# nrf51822-button.net
KiCad netlist of a schematic drawn in EAGLE
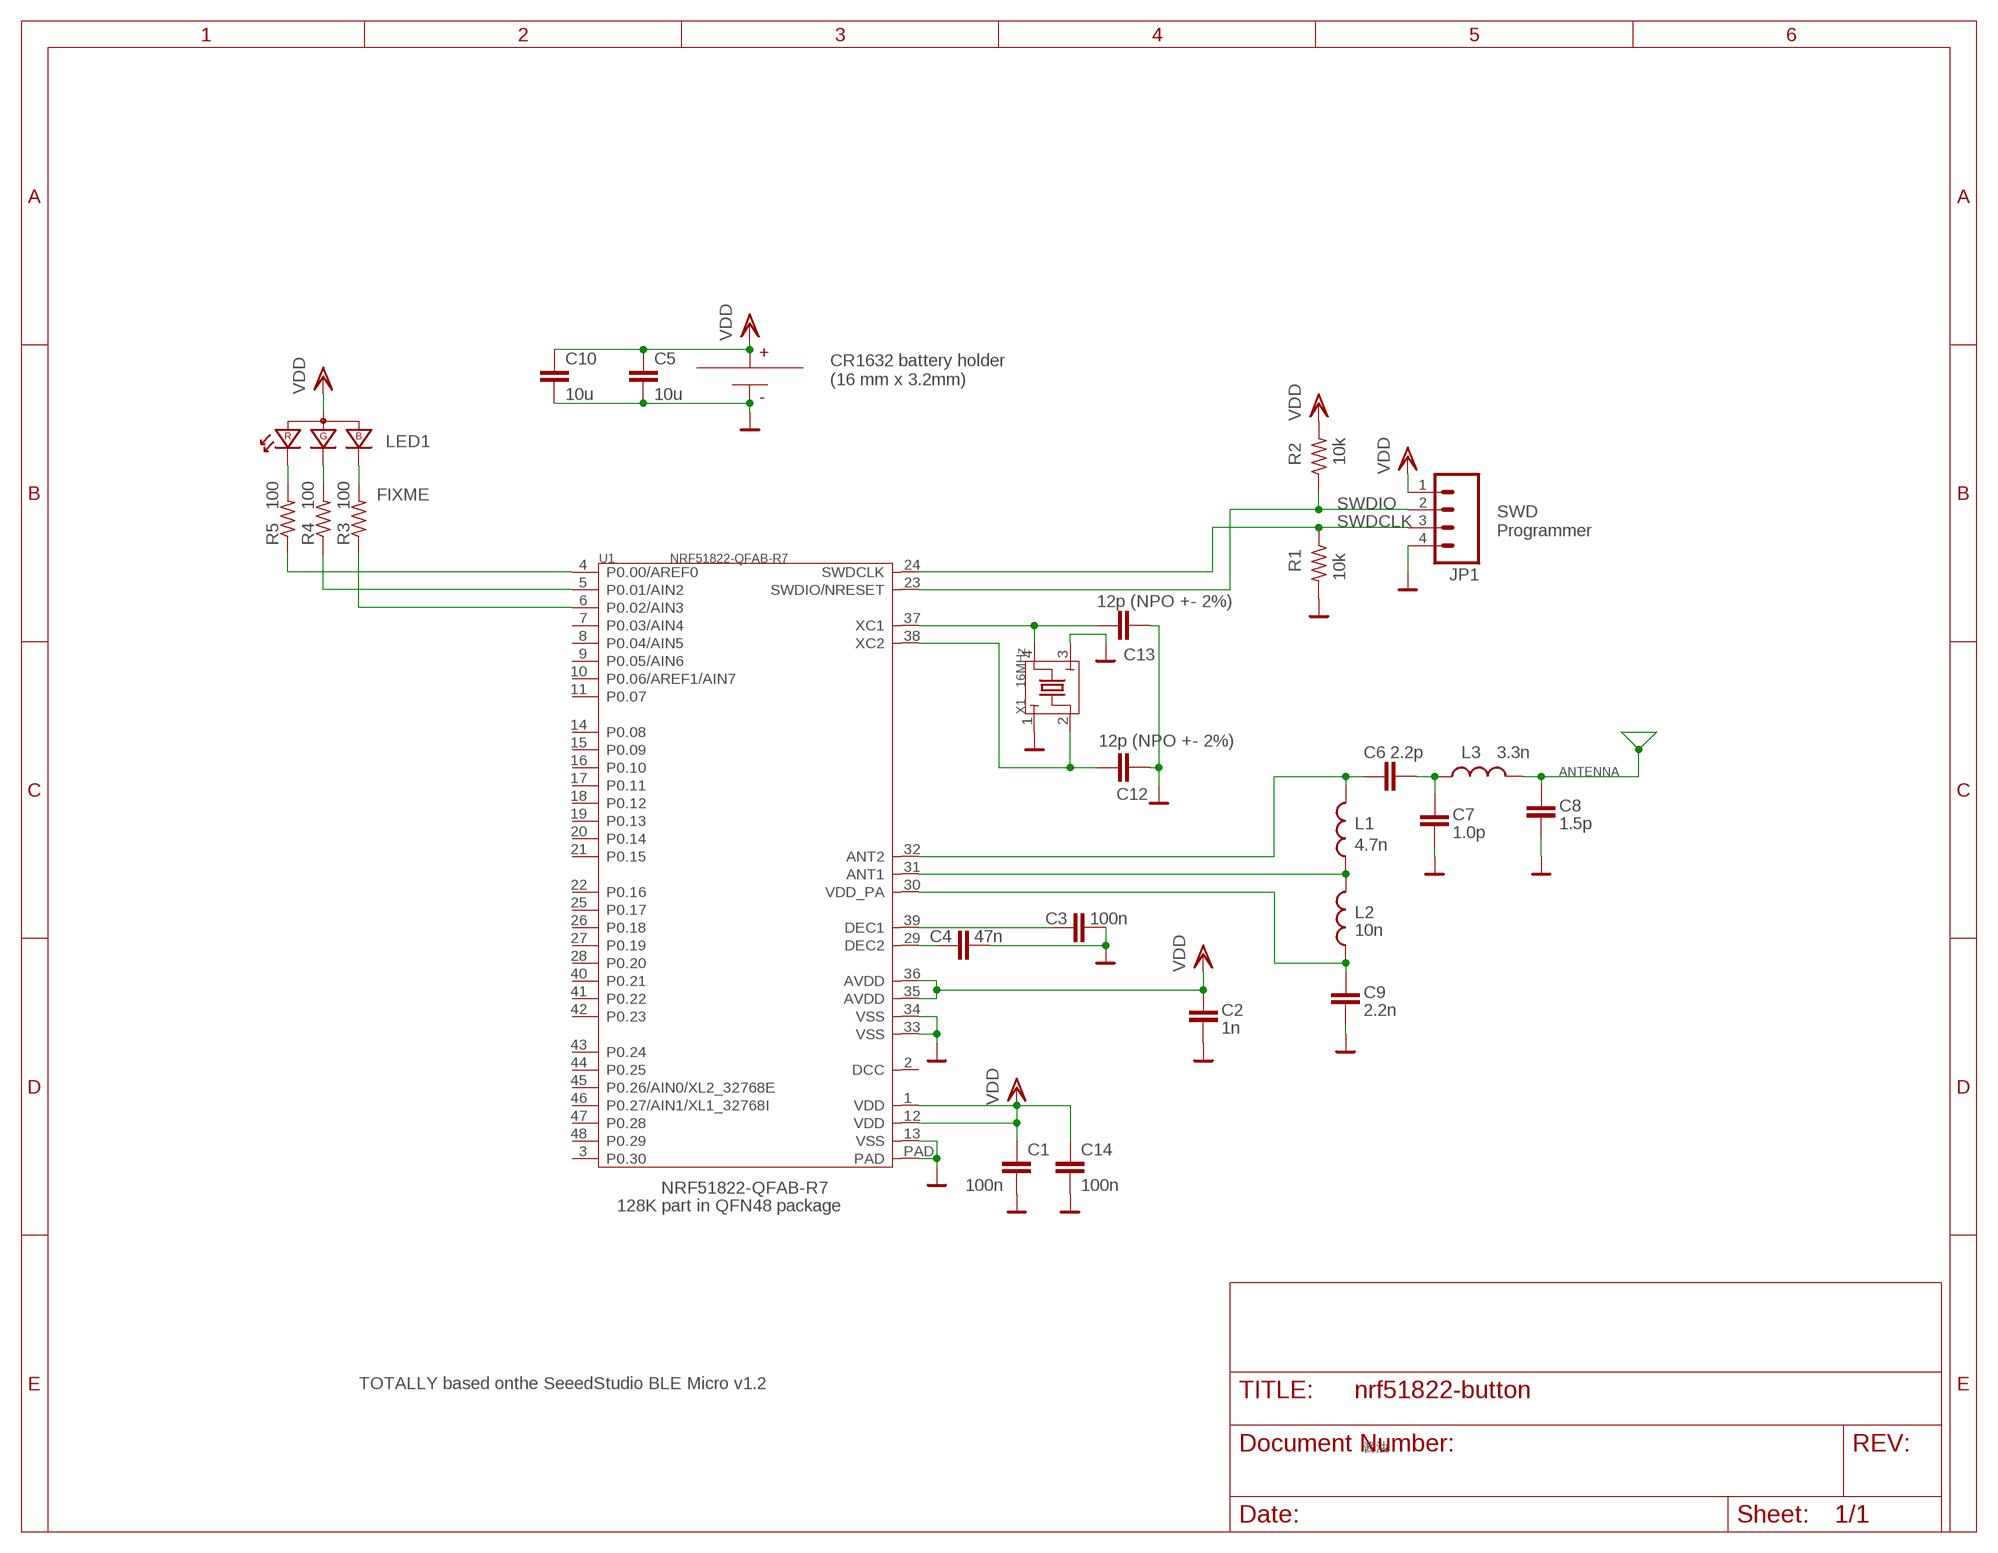
[diagram p0: schematic, sheet 1]

(export (version "E")
  (design (tool "Eeschema 10.0.6"))
  (components
    (comp (ref "B1")
      (value "CON-COINCEL-HOLDER-KEYSTONE-3012TR")
      (footprint "eagle-import:16MM-COINCELL-KEYSTONE")
      (libsource (lib "eagle-import") (part "CON-COINCEL-HOLDER-KEYSTONE-3012TR"))
    )
    (comp (ref "C1")
      (value "100n")
      (footprint "eagle-import:.0402-C-NOSILK")
      (libsource (lib "eagle-import") (part "C-EU0402-C-NOSILK"))
    )
    (comp (ref "C2")
      (value "1n")
      (footprint "eagle-import:.0402-C-NOSILK")
      (libsource (lib "eagle-import") (part "C-EU0402-C-NOSILK"))
    )
    (comp (ref "C3")
      (value "100n")
      (footprint "eagle-import:.0402-C-NOSILK")
      (libsource (lib "eagle-import") (part "C-EU0402-C-NOSILK"))
    )
    (comp (ref "C4")
      (value "47n")
      (footprint "eagle-import:.0402-C-NOSILK")
      (libsource (lib "eagle-import") (part "C-EU0402-C-NOSILK"))
    )
    (comp (ref "C5")
      (value "10u")
      (footprint "eagle-import:.0805-B-NOSILK")
      (libsource (lib "eagle-import") (part "C-EU0805-B-NOSILK"))
    )
    (comp (ref "C6")
      (value "2.2p")
      (footprint "eagle-import:.0402-C-NOSILK")
      (libsource (lib "eagle-import") (part "C-EU0402-C-NOSILK"))
    )
    (comp (ref "C7")
      (value "1.0p")
      (footprint "eagle-import:.0402-C-NOSILK")
      (libsource (lib "eagle-import") (part "C-EU0402-C-NOSILK"))
    )
    (comp (ref "C8")
      (value "1.5p")
      (footprint "eagle-import:.0402-C-NOSILK")
      (libsource (lib "eagle-import") (part "C-EU0402-C-NOSILK"))
    )
    (comp (ref "C9")
      (value "2.2n")
      (footprint "eagle-import:.0402-C-NOSILK")
      (libsource (lib "eagle-import") (part "C-EU0402-C-NOSILK"))
    )
    (comp (ref "C10")
      (value "10u")
      (footprint "eagle-import:.0805-B-NOSILK")
      (libsource (lib "eagle-import") (part "C-EU0805-B-NOSILK"))
    )
    (comp (ref "C12")
      (value "12p (NPO +- 2%)")
      (footprint "eagle-import:.0402-C-NOSILK")
      (libsource (lib "eagle-import") (part "C-EU0402-C-NOSILK"))
    )
    (comp (ref "C13")
      (value "12p (NPO +- 2%)")
      (footprint "eagle-import:.0402-C-NOSILK")
      (libsource (lib "eagle-import") (part "C-EU0402-C-NOSILK"))
    )
    (comp (ref "C14")
      (value "100n")
      (footprint "eagle-import:.0402-C-NOSILK")
      (libsource (lib "eagle-import") (part "C-EU0402-C-NOSILK"))
    )
    (comp (ref "JP1")
      (value "M041.27MM")
      (footprint "eagle-import:1X04-1.27MM")
      (libsource (lib "eagle-import") (part "M041.27MM"))
    )
    (comp (ref "L1")
      (value "4.7n")
      (footprint "eagle-import:.0402-C-NOSILK")
      (libsource (lib "eagle-import") (part "L-US0402-C-NOSILK"))
    )
    (comp (ref "L2")
      (value "10n")
      (footprint "eagle-import:.0402-C-NOSILK")
      (libsource (lib "eagle-import") (part "L-US0402-C-NOSILK"))
    )
    (comp (ref "L3")
      (value "3.3n")
      (footprint "eagle-import:.0402-C-NOSILK")
      (libsource (lib "eagle-import") (part "L-US0402-C-NOSILK"))
    )
    (comp (ref "LED1")
      (value "LED_RGB_COMMON_ANODE-1.6X1.26")
      (footprint "eagle-import:KINGBRITE_RGBLED_1.6X1.26")
      (libsource (lib "eagle-import") (part "LED_RGB_COMMON_ANODE-1.6X1.26"))
    )
    (comp (ref "R1")
      (value "10k")
      (footprint "eagle-import:.0402-C-NOSILK")
      (libsource (lib "eagle-import") (part "R-US_0402-C-NOSILK"))
    )
    (comp (ref "R2")
      (value "10k")
      (footprint "eagle-import:.0402-C-NOSILK")
      (libsource (lib "eagle-import") (part "R-US_0402-C-NOSILK"))
    )
    (comp (ref "R3")
      (value "100")
      (footprint "eagle-import:.0402-C-NOSILK")
      (libsource (lib "eagle-import") (part "R-US_0402-C-NOSILK"))
    )
    (comp (ref "R4")
      (value "100")
      (footprint "eagle-import:.0402-C-NOSILK")
      (libsource (lib "eagle-import") (part "R-US_0402-C-NOSILK"))
    )
    (comp (ref "R5")
      (value "100")
      (footprint "eagle-import:.0402-C-NOSILK")
      (libsource (lib "eagle-import") (part "R-US_0402-C-NOSILK"))
    )
    (comp (ref "U1")
      (value "NRF51822-QFAB-R7")
      (footprint "eagle-import:QFN48-6X6MM")
      (libsource (lib "eagle-import") (part "NRF51822"))
    )
    (comp (ref "X1")
      (value "16MHz")
      (footprint "eagle-import:2520")
      (libsource (lib "eagle-import") (part "CRYSTAL'-2520'"))
    )
  )
  (nets
    (net (code "1") (name "/ANTENNA") (class "Default")
      (node (ref "C8") (pin "2") (pinfunction "2_2") (pintype "passive"))
      (node (ref "L3") (pin "2") (pinfunction "2_2") (pintype "passive"))
    )
    (net (code "2") (name "/SWDCLK") (class "Default")
      (node (ref "JP1") (pin "3") (pinfunction "3_3") (pintype "passive"))
      (node (ref "R1") (pin "1") (pinfunction "1_1") (pintype "passive"))
      (node (ref "U1") (pin "24") (pinfunction "SWDCLK_24") (pintype "bidirectional"))
    )
    (net (code "3") (name "/SWDIO") (class "Default")
      (node (ref "JP1") (pin "2") (pinfunction "2_2") (pintype "passive"))
      (node (ref "R2") (pin "1") (pinfunction "1_1") (pintype "passive"))
      (node (ref "U1") (pin "23") (pinfunction "SWDIO/NRESET_23") (pintype "bidirectional"))
    )
    (net (code "4") (name "GND") (class "Default")
      (node (ref "B1") (pin "NEG") (pinfunction "NEG_NEG") (pintype "power_in"))
      (node (ref "C1") (pin "2") (pinfunction "2_2") (pintype "passive"))
      (node (ref "C10") (pin "2") (pinfunction "2_2") (pintype "passive"))
      (node (ref "C12") (pin "2") (pinfunction "2_2") (pintype "passive"))
      (node (ref "C13") (pin "2") (pinfunction "2_2") (pintype "passive"))
      (node (ref "C14") (pin "2") (pinfunction "2_2") (pintype "passive"))
      (node (ref "C2") (pin "2") (pinfunction "2_2") (pintype "passive"))
      (node (ref "C3") (pin "2") (pinfunction "2_2") (pintype "passive"))
      (node (ref "C4") (pin "2") (pinfunction "2_2") (pintype "passive"))
      (node (ref "C5") (pin "2") (pinfunction "2_2") (pintype "passive"))
      (node (ref "C7") (pin "1") (pinfunction "1_1") (pintype "passive"))
      (node (ref "C8") (pin "1") (pinfunction "1_1") (pintype "passive"))
      (node (ref "C9") (pin "2") (pinfunction "2_2") (pintype "passive"))
      (node (ref "JP1") (pin "4") (pinfunction "4_4") (pintype "passive"))
      (node (ref "R1") (pin "2") (pinfunction "2_2") (pintype "passive"))
      (node (ref "U1") (pin "13") (pinfunction "VSS_13") (pintype "bidirectional"))
      (node (ref "U1") (pin "33") (pinfunction "VSS_33") (pintype "bidirectional"))
      (node (ref "U1") (pin "34") (pinfunction "VSS_34") (pintype "bidirectional"))
      (node (ref "U1") (pin "PAD") (pinfunction "PAD_PAD") (pintype "bidirectional"))
      (node (ref "X1") (pin "1") (pinfunction "1_1") (pintype "bidirectional"))
      (node (ref "X1") (pin "3") (pinfunction "3_3") (pintype "bidirectional"))
    )
    (net (code "5") (name "Net-(C6-Pad2)") (class "Default")
      (node (ref "C6") (pin "2") (pinfunction "2_2") (pintype "passive"))
      (node (ref "C7") (pin "2") (pinfunction "2_2") (pintype "passive"))
      (node (ref "L3") (pin "1") (pinfunction "1_1") (pintype "passive"))
    )
    (net (code "6") (name "Net-(LED1-BK)") (class "Default")
      (node (ref "LED1") (pin "1") (pinfunction "BK_1") (pintype "passive"))
      (node (ref "R3") (pin "2") (pinfunction "2_2") (pintype "passive"))
    )
    (net (code "7") (name "Net-(LED1-GK)") (class "Default")
      (node (ref "LED1") (pin "4") (pinfunction "GK_4") (pintype "passive"))
      (node (ref "R4") (pin "2") (pinfunction "2_2") (pintype "passive"))
    )
    (net (code "8") (name "Net-(LED1-RK)") (class "Default")
      (node (ref "LED1") (pin "3") (pinfunction "RK_3") (pintype "passive"))
      (node (ref "R5") (pin "2") (pinfunction "2_2") (pintype "passive"))
    )
    (net (code "9") (name "Net-(U1-ANT1)") (class "Default")
      (node (ref "L1") (pin "1") (pinfunction "1_1") (pintype "passive"))
      (node (ref "L2") (pin "2") (pinfunction "2_2") (pintype "passive"))
      (node (ref "U1") (pin "31") (pinfunction "ANT1_31") (pintype "bidirectional"))
    )
    (net (code "10") (name "Net-(U1-ANT2)") (class "Default")
      (node (ref "C6") (pin "1") (pinfunction "1_1") (pintype "passive"))
      (node (ref "L1") (pin "2") (pinfunction "2_2") (pintype "passive"))
      (node (ref "U1") (pin "32") (pinfunction "ANT2_32") (pintype "bidirectional"))
    )
    (net (code "11") (name "Net-(U1-DEC1)") (class "Default")
      (node (ref "C3") (pin "1") (pinfunction "1_1") (pintype "passive"))
      (node (ref "U1") (pin "39") (pinfunction "DEC1_39") (pintype "bidirectional"))
    )
    (net (code "12") (name "Net-(U1-DEC2)") (class "Default")
      (node (ref "C4") (pin "1") (pinfunction "1_1") (pintype "passive"))
      (node (ref "U1") (pin "29") (pinfunction "DEC2_29") (pintype "bidirectional"))
    )
    (net (code "13") (name "Net-(U1-P0.00{slash}AREF0)") (class "Default")
      (node (ref "R5") (pin "1") (pinfunction "1_1") (pintype "passive"))
      (node (ref "U1") (pin "4") (pinfunction "P0.00/AREF0_4") (pintype "bidirectional"))
    )
    (net (code "14") (name "Net-(U1-P0.01{slash}AIN2)") (class "Default")
      (node (ref "R4") (pin "1") (pinfunction "1_1") (pintype "passive"))
      (node (ref "U1") (pin "5") (pinfunction "P0.01/AIN2_5") (pintype "bidirectional"))
    )
    (net (code "15") (name "Net-(U1-P0.02{slash}AIN3)") (class "Default")
      (node (ref "R3") (pin "1") (pinfunction "1_1") (pintype "passive"))
      (node (ref "U1") (pin "6") (pinfunction "P0.02/AIN3_6") (pintype "bidirectional"))
    )
    (net (code "16") (name "Net-(U1-VDD_PA)") (class "Default")
      (node (ref "C9") (pin "1") (pinfunction "1_1") (pintype "passive"))
      (node (ref "L2") (pin "1") (pinfunction "1_1") (pintype "passive"))
      (node (ref "U1") (pin "30") (pinfunction "VDD_PA_30") (pintype "bidirectional"))
    )
    (net (code "17") (name "Net-(U1-XC1)") (class "Default")
      (node (ref "C13") (pin "1") (pinfunction "1_1") (pintype "passive"))
      (node (ref "U1") (pin "37") (pinfunction "XC1_37") (pintype "bidirectional"))
      (node (ref "X1") (pin "4") (pinfunction "4_4") (pintype "passive"))
    )
    (net (code "18") (name "Net-(U1-XC2)") (class "Default")
      (node (ref "C12") (pin "1") (pinfunction "1_1") (pintype "passive"))
      (node (ref "U1") (pin "38") (pinfunction "XC2_38") (pintype "bidirectional"))
      (node (ref "X1") (pin "2") (pinfunction "2_2") (pintype "passive"))
    )
    (net (code "19") (name "VDD") (class "Default")
      (node (ref "B1") (pin "POS@1") (pinfunction "POS_POS@1") (pintype "power_in"))
      (node (ref "B1") (pin "POS@2") (pinfunction "POS_POS@2") (pintype "power_in"))
      (node (ref "C1") (pin "1") (pinfunction "1_1") (pintype "passive"))
      (node (ref "C10") (pin "1") (pinfunction "1_1") (pintype "passive"))
      (node (ref "C14") (pin "1") (pinfunction "1_1") (pintype "passive"))
      (node (ref "C2") (pin "1") (pinfunction "1_1") (pintype "passive"))
      (node (ref "C5") (pin "1") (pinfunction "1_1") (pintype "passive"))
      (node (ref "JP1") (pin "1") (pinfunction "1_1") (pintype "passive"))
      (node (ref "LED1") (pin "2") (pinfunction "COMMON_ANODE_2") (pintype "passive"))
      (node (ref "R2") (pin "2") (pinfunction "2_2") (pintype "passive"))
      (node (ref "U1") (pin "1") (pinfunction "VDD_1") (pintype "bidirectional"))
      (node (ref "U1") (pin "12") (pinfunction "VDD_12") (pintype "bidirectional"))
      (node (ref "U1") (pin "35") (pinfunction "AVDD_35") (pintype "bidirectional"))
      (node (ref "U1") (pin "36") (pinfunction "AVDD_36") (pintype "bidirectional"))
    )
    (net (code "20") (name "unconnected-(U1-DCC-Pad2)") (class "Default")
      (node (ref "U1") (pin "2") (pinfunction "DCC_2") (pintype "bidirectional"))
    )
    (net (code "21") (name "unconnected-(U1-P0.03{slash}AIN4-Pad7)") (class "Default")
      (node (ref "U1") (pin "7") (pinfunction "P0.03/AIN4_7") (pintype "bidirectional"))
    )
    (net (code "22") (name "unconnected-(U1-P0.04{slash}AIN5-Pad8)") (class "Default")
      (node (ref "U1") (pin "8") (pinfunction "P0.04/AIN5_8") (pintype "bidirectional"))
    )
    (net (code "23") (name "unconnected-(U1-P0.05{slash}AIN6-Pad9)") (class "Default")
      (node (ref "U1") (pin "9") (pinfunction "P0.05/AIN6_9") (pintype "bidirectional"))
    )
    (net (code "24") (name "unconnected-(U1-P0.06{slash}AREF1{slash}AIN7-Pad10)") (class "Default")
      (node (ref "U1") (pin "10") (pinfunction "P0.06/AREF1/AIN7_10") (pintype "bidirectional"))
    )
    (net (code "25") (name "unconnected-(U1-P0.07-Pad11)") (class "Default")
      (node (ref "U1") (pin "11") (pinfunction "P0.07_11") (pintype "bidirectional"))
    )
    (net (code "26") (name "unconnected-(U1-P0.08-Pad14)") (class "Default")
      (node (ref "U1") (pin "14") (pinfunction "P0.08_14") (pintype "bidirectional"))
    )
    (net (code "27") (name "unconnected-(U1-P0.09-Pad15)") (class "Default")
      (node (ref "U1") (pin "15") (pinfunction "P0.09_15") (pintype "bidirectional"))
    )
    (net (code "28") (name "unconnected-(U1-P0.10-Pad16)") (class "Default")
      (node (ref "U1") (pin "16") (pinfunction "P0.10_16") (pintype "bidirectional"))
    )
    (net (code "29") (name "unconnected-(U1-P0.11-Pad17)") (class "Default")
      (node (ref "U1") (pin "17") (pinfunction "P0.11_17") (pintype "bidirectional"))
    )
    (net (code "30") (name "unconnected-(U1-P0.12-Pad18)") (class "Default")
      (node (ref "U1") (pin "18") (pinfunction "P0.12_18") (pintype "bidirectional"))
    )
    (net (code "31") (name "unconnected-(U1-P0.13-Pad19)") (class "Default")
      (node (ref "U1") (pin "19") (pinfunction "P0.13_19") (pintype "bidirectional"))
    )
    (net (code "32") (name "unconnected-(U1-P0.14-Pad20)") (class "Default")
      (node (ref "U1") (pin "20") (pinfunction "P0.14_20") (pintype "bidirectional"))
    )
    (net (code "33") (name "unconnected-(U1-P0.15-Pad21)") (class "Default")
      (node (ref "U1") (pin "21") (pinfunction "P0.15_21") (pintype "bidirectional"))
    )
    (net (code "34") (name "unconnected-(U1-P0.16-Pad22)") (class "Default")
      (node (ref "U1") (pin "22") (pinfunction "P0.16_22") (pintype "bidirectional"))
    )
    (net (code "35") (name "unconnected-(U1-P0.17-Pad25)") (class "Default")
      (node (ref "U1") (pin "25") (pinfunction "P0.17_25") (pintype "bidirectional"))
    )
    (net (code "36") (name "unconnected-(U1-P0.18-Pad26)") (class "Default")
      (node (ref "U1") (pin "26") (pinfunction "P0.18_26") (pintype "bidirectional"))
    )
    (net (code "37") (name "unconnected-(U1-P0.19-Pad27)") (class "Default")
      (node (ref "U1") (pin "27") (pinfunction "P0.19_27") (pintype "bidirectional"))
    )
    (net (code "38") (name "unconnected-(U1-P0.20-Pad28)") (class "Default")
      (node (ref "U1") (pin "28") (pinfunction "P0.20_28") (pintype "bidirectional"))
    )
    (net (code "39") (name "unconnected-(U1-P0.21-Pad40)") (class "Default")
      (node (ref "U1") (pin "40") (pinfunction "P0.21_40") (pintype "bidirectional"))
    )
    (net (code "40") (name "unconnected-(U1-P0.22-Pad41)") (class "Default")
      (node (ref "U1") (pin "41") (pinfunction "P0.22_41") (pintype "bidirectional"))
    )
    (net (code "41") (name "unconnected-(U1-P0.23-Pad42)") (class "Default")
      (node (ref "U1") (pin "42") (pinfunction "P0.23_42") (pintype "bidirectional"))
    )
    (net (code "42") (name "unconnected-(U1-P0.24-Pad43)") (class "Default")
      (node (ref "U1") (pin "43") (pinfunction "P0.24_43") (pintype "bidirectional"))
    )
    (net (code "43") (name "unconnected-(U1-P0.25-Pad44)") (class "Default")
      (node (ref "U1") (pin "44") (pinfunction "P0.25_44") (pintype "bidirectional"))
    )
    (net (code "44") (name "unconnected-(U1-P0.26{slash}AIN0{slash}XL2_32768E-Pad45)") (class "Default")
      (node (ref "U1") (pin "45") (pinfunction "P0.26/AIN0/XL2_32768E_45") (pintype "bidirectional"))
    )
    (net (code "45") (name "unconnected-(U1-P0.27{slash}AIN1{slash}XL1_32768I-Pad46)") (class "Default")
      (node (ref "U1") (pin "46") (pinfunction "P0.27/AIN1/XL1_32768I_46") (pintype "bidirectional"))
    )
    (net (code "46") (name "unconnected-(U1-P0.28-Pad47)") (class "Default")
      (node (ref "U1") (pin "47") (pinfunction "P0.28_47") (pintype "bidirectional"))
    )
    (net (code "47") (name "unconnected-(U1-P0.29-Pad48)") (class "Default")
      (node (ref "U1") (pin "48") (pinfunction "P0.29_48") (pintype "bidirectional"))
    )
    (net (code "48") (name "unconnected-(U1-P0.30-Pad3)") (class "Default")
      (node (ref "U1") (pin "3") (pinfunction "P0.30_3") (pintype "bidirectional"))
    )
  )
)
